# stm32f4.net
KiCad netlist of a schematic drawn in EAGLE
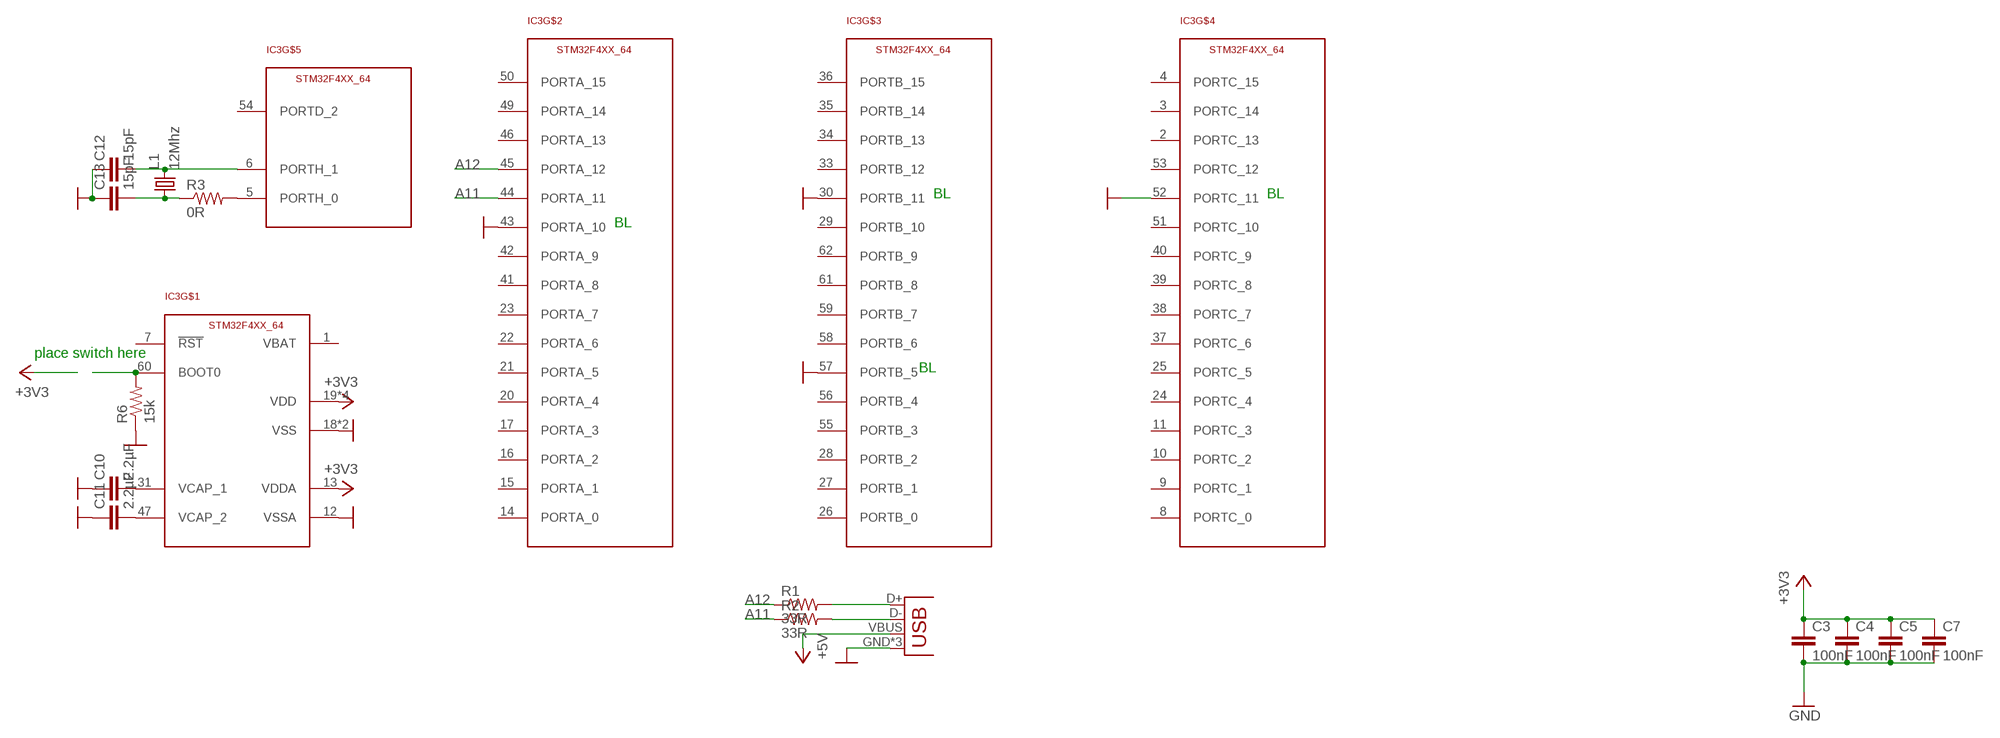
[diagram p0: schematic, sheet 1]

(export (version "E")
  (design (tool "Eeschema 10.0.6"))
  (components
    (comp (ref "C3")
      (value "100nF")
      (footprint "eagle-import:0402-CAP")
      (libsource (lib "eagle-import") (part "CAP0402-CAP"))
    )
    (comp (ref "C4")
      (value "100nF")
      (footprint "eagle-import:0402-CAP")
      (libsource (lib "eagle-import") (part "CAP0402-CAP"))
    )
    (comp (ref "C5")
      (value "100nF")
      (footprint "eagle-import:0402-CAP")
      (libsource (lib "eagle-import") (part "CAP0402-CAP"))
    )
    (comp (ref "C7")
      (value "100nF")
      (footprint "eagle-import:0402-CAP")
      (libsource (lib "eagle-import") (part "CAP0402-CAP"))
    )
    (comp (ref "C10")
      (value "2.2µF")
      (footprint "eagle-import:0805")
      (libsource (lib "eagle-import") (part "CAP0805"))
    )
    (comp (ref "C11")
      (value "2.2µF")
      (footprint "eagle-import:0805")
      (libsource (lib "eagle-import") (part "CAP0805"))
    )
    (comp (ref "C12")
      (value "15pF")
      (footprint "eagle-import:0402-CAP")
      (libsource (lib "eagle-import") (part "CAP0402-CAP"))
    )
    (comp (ref "C13")
      (value "15pF")
      (footprint "eagle-import:0402-CAP")
      (libsource (lib "eagle-import") (part "CAP0402-CAP"))
    )
    (comp (ref "IC3")
      (value "STM32F4XX_64")
      (footprint "eagle-import:TQFP64")
      (libsource (lib "eagle-import") (part "STM32F4XX_64"))
    )
    (comp (ref "JP1")
      (value "USB-MICROB")
      (footprint "eagle-import:USB-MICROB")
      (libsource (lib "eagle-import") (part "USB-MICROB"))
    )
    (comp (ref "L1")
      (value "12Mhz")
      (footprint "eagle-import:X22")
      (libsource (lib "eagle-import") (part "X22-OSCILLATOR"))
    )
    (comp (ref "R1")
      (value "33R")
      (footprint "eagle-import:0402-RES")
      (libsource (lib "eagle-import") (part "SparkFun-Resistors_RESISTOR0402-RES"))
    )
    (comp (ref "R2")
      (value "33R")
      (footprint "eagle-import:0402-RES")
      (libsource (lib "eagle-import") (part "SparkFun-Resistors_RESISTOR0402-RES"))
    )
    (comp (ref "R3")
      (value "0R")
      (footprint "eagle-import:0402-RES")
      (libsource (lib "eagle-import") (part "SparkFun-Resistors_RESISTOR0402-RES"))
    )
    (comp (ref "R6")
      (value "15k")
      (footprint "eagle-import:0402-RES")
      (libsource (lib "eagle-import") (part "RESISTOR0402-RES"))
    )
  )
  (nets
    (net (code "1") (name "+3V3") (class "Default")
      (node (ref "C3") (pin "1") (pinfunction "1_1") (pintype "passive"))
      (node (ref "C4") (pin "1") (pinfunction "1_1") (pintype "passive"))
      (node (ref "C5") (pin "1") (pinfunction "1_1") (pintype "passive"))
      (node (ref "C7") (pin "1") (pinfunction "1_1") (pintype "passive"))
      (node (ref "IC3") (pin "13") (pinfunction "VDDA_13") (pintype "bidirectional"))
      (node (ref "IC3") (pin "19") (pinfunction "VDD_19") (pintype "bidirectional"))
      (node (ref "IC3") (pin "32") (pinfunction "VDD_32") (pintype "bidirectional"))
      (node (ref "IC3") (pin "48") (pinfunction "VDD_48") (pintype "bidirectional"))
      (node (ref "IC3") (pin "64") (pinfunction "VDD_64") (pintype "bidirectional"))
    )
    (net (code "2") (name "+5V") (class "Default")
      (node (ref "JP1") (pin "VBUS") (pinfunction "VBUS_VBUS") (pintype "bidirectional"))
    )
    (net (code "3") (name "/A11") (class "Default")
      (node (ref "IC3") (pin "44") (pinfunction "PORTA_11_44") (pintype "bidirectional"))
      (node (ref "R2") (pin "1") (pinfunction "1_1") (pintype "passive"))
    )
    (net (code "4") (name "/A12") (class "Default")
      (node (ref "IC3") (pin "45") (pinfunction "PORTA_12_45") (pintype "bidirectional"))
      (node (ref "R1") (pin "1") (pinfunction "1_1") (pintype "passive"))
    )
    (net (code "5") (name "GND") (class "Default")
      (node (ref "C10") (pin "1") (pinfunction "1_1") (pintype "passive"))
      (node (ref "C11") (pin "1") (pinfunction "1_1") (pintype "passive"))
      (node (ref "C12") (pin "1") (pinfunction "1_1") (pintype "passive"))
      (node (ref "C13") (pin "1") (pinfunction "1_1") (pintype "passive"))
      (node (ref "C3") (pin "2") (pinfunction "2_2") (pintype "passive"))
      (node (ref "C4") (pin "2") (pinfunction "2_2") (pintype "passive"))
      (node (ref "C5") (pin "2") (pinfunction "2_2") (pintype "passive"))
      (node (ref "C7") (pin "2") (pinfunction "2_2") (pintype "passive"))
      (node (ref "IC3") (pin "12") (pinfunction "VSSA_12") (pintype "bidirectional"))
      (node (ref "IC3") (pin "18") (pinfunction "VSS_18") (pintype "bidirectional"))
      (node (ref "IC3") (pin "30") (pinfunction "PORTB_11_30") (pintype "bidirectional"))
      (node (ref "IC3") (pin "43") (pinfunction "PORTA_10_43") (pintype "bidirectional"))
      (node (ref "IC3") (pin "52") (pinfunction "PORTC_11_52") (pintype "bidirectional"))
      (node (ref "IC3") (pin "57") (pinfunction "PORTB_5_57") (pintype "bidirectional"))
      (node (ref "IC3") (pin "63") (pinfunction "VSS_63") (pintype "bidirectional"))
      (node (ref "JP1") (pin "GND") (pinfunction "GND_GND") (pintype "bidirectional"))
      (node (ref "JP1") (pin "MT1") (pinfunction "GND_MT1") (pintype "bidirectional"))
      (node (ref "JP1") (pin "MT2") (pinfunction "GND_MT2") (pintype "bidirectional"))
      (node (ref "R6") (pin "1") (pinfunction "1_1") (pintype "passive"))
    )
    (net (code "6") (name "Net-(C13-Pad2)") (class "Default")
      (node (ref "C13") (pin "2") (pinfunction "2_2") (pintype "passive"))
      (node (ref "L1") (pin "1") (pinfunction "1_1") (pintype "passive"))
      (node (ref "R3") (pin "1") (pinfunction "1_1") (pintype "passive"))
    )
    (net (code "7") (name "Net-(IC3A-BOOT0)") (class "Default")
      (node (ref "IC3") (pin "60") (pinfunction "BOOT0_60") (pintype "bidirectional"))
      (node (ref "R6") (pin "2") (pinfunction "2_2") (pintype "passive"))
    )
    (net (code "8") (name "Net-(IC3A-VCAP_1)") (class "Default")
      (node (ref "C10") (pin "2") (pinfunction "2_2") (pintype "passive"))
      (node (ref "IC3") (pin "31") (pinfunction "VCAP_1_31") (pintype "bidirectional"))
    )
    (net (code "9") (name "Net-(IC3A-VCAP_2)") (class "Default")
      (node (ref "C11") (pin "2") (pinfunction "2_2") (pintype "passive"))
      (node (ref "IC3") (pin "47") (pinfunction "VCAP_2_47") (pintype "bidirectional"))
    )
    (net (code "10") (name "Net-(IC3E-PORTH_0)") (class "Default")
      (node (ref "IC3") (pin "5") (pinfunction "PORTH_0_5") (pintype "bidirectional"))
      (node (ref "R3") (pin "2") (pinfunction "2_2") (pintype "passive"))
    )
    (net (code "11") (name "Net-(IC3E-PORTH_1)") (class "Default")
      (node (ref "C12") (pin "2") (pinfunction "2_2") (pintype "passive"))
      (node (ref "IC3") (pin "6") (pinfunction "PORTH_1_6") (pintype "bidirectional"))
      (node (ref "L1") (pin "3") (pinfunction "2_3") (pintype "passive"))
    )
    (net (code "12") (name "Net-(JP1-PadD+)") (class "Default")
      (node (ref "JP1") (pin "D+") (pinfunction "D+_D+") (pintype "bidirectional"))
      (node (ref "R1") (pin "2") (pinfunction "2_2") (pintype "passive"))
    )
    (net (code "13") (name "Net-(JP1-PadD-)") (class "Default")
      (node (ref "JP1") (pin "D-") (pinfunction "D-_D-") (pintype "bidirectional"))
      (node (ref "R2") (pin "2") (pinfunction "2_2") (pintype "passive"))
    )
    (net (code "14") (name "unconnected-(IC3A-VBAT-Pad1)") (class "Default")
      (node (ref "IC3") (pin "1") (pinfunction "VBAT_1") (pintype "bidirectional"))
    )
    (net (code "15") (name "unconnected-(IC3A-~{RST}-Pad7)") (class "Default")
      (node (ref "IC3") (pin "7") (pinfunction "~{RST}_7") (pintype "bidirectional"))
    )
    (net (code "16") (name "unconnected-(IC3B-PORTA_0-Pad14)") (class "Default")
      (node (ref "IC3") (pin "14") (pinfunction "PORTA_0_14") (pintype "bidirectional"))
    )
    (net (code "17") (name "unconnected-(IC3B-PORTA_1-Pad15)") (class "Default")
      (node (ref "IC3") (pin "15") (pinfunction "PORTA_1_15") (pintype "bidirectional"))
    )
    (net (code "18") (name "unconnected-(IC3B-PORTA_2-Pad16)") (class "Default")
      (node (ref "IC3") (pin "16") (pinfunction "PORTA_2_16") (pintype "bidirectional"))
    )
    (net (code "19") (name "unconnected-(IC3B-PORTA_3-Pad17)") (class "Default")
      (node (ref "IC3") (pin "17") (pinfunction "PORTA_3_17") (pintype "bidirectional"))
    )
    (net (code "20") (name "unconnected-(IC3B-PORTA_4-Pad20)") (class "Default")
      (node (ref "IC3") (pin "20") (pinfunction "PORTA_4_20") (pintype "bidirectional"))
    )
    (net (code "21") (name "unconnected-(IC3B-PORTA_5-Pad21)") (class "Default")
      (node (ref "IC3") (pin "21") (pinfunction "PORTA_5_21") (pintype "bidirectional"))
    )
    (net (code "22") (name "unconnected-(IC3B-PORTA_6-Pad22)") (class "Default")
      (node (ref "IC3") (pin "22") (pinfunction "PORTA_6_22") (pintype "bidirectional"))
    )
    (net (code "23") (name "unconnected-(IC3B-PORTA_7-Pad23)") (class "Default")
      (node (ref "IC3") (pin "23") (pinfunction "PORTA_7_23") (pintype "bidirectional"))
    )
    (net (code "24") (name "unconnected-(IC3B-PORTA_8-Pad41)") (class "Default")
      (node (ref "IC3") (pin "41") (pinfunction "PORTA_8_41") (pintype "bidirectional"))
    )
    (net (code "25") (name "unconnected-(IC3B-PORTA_9-Pad42)") (class "Default")
      (node (ref "IC3") (pin "42") (pinfunction "PORTA_9_42") (pintype "bidirectional"))
    )
    (net (code "26") (name "unconnected-(IC3B-PORTA_13-Pad46)") (class "Default")
      (node (ref "IC3") (pin "46") (pinfunction "PORTA_13_46") (pintype "bidirectional"))
    )
    (net (code "27") (name "unconnected-(IC3B-PORTA_14-Pad49)") (class "Default")
      (node (ref "IC3") (pin "49") (pinfunction "PORTA_14_49") (pintype "bidirectional"))
    )
    (net (code "28") (name "unconnected-(IC3B-PORTA_15-Pad50)") (class "Default")
      (node (ref "IC3") (pin "50") (pinfunction "PORTA_15_50") (pintype "bidirectional"))
    )
    (net (code "29") (name "unconnected-(IC3C-PORTB_0-Pad26)") (class "Default")
      (node (ref "IC3") (pin "26") (pinfunction "PORTB_0_26") (pintype "bidirectional"))
    )
    (net (code "30") (name "unconnected-(IC3C-PORTB_1-Pad27)") (class "Default")
      (node (ref "IC3") (pin "27") (pinfunction "PORTB_1_27") (pintype "bidirectional"))
    )
    (net (code "31") (name "unconnected-(IC3C-PORTB_2-Pad28)") (class "Default")
      (node (ref "IC3") (pin "28") (pinfunction "PORTB_2_28") (pintype "bidirectional"))
    )
    (net (code "32") (name "unconnected-(IC3C-PORTB_3-Pad55)") (class "Default")
      (node (ref "IC3") (pin "55") (pinfunction "PORTB_3_55") (pintype "bidirectional"))
    )
    (net (code "33") (name "unconnected-(IC3C-PORTB_4-Pad56)") (class "Default")
      (node (ref "IC3") (pin "56") (pinfunction "PORTB_4_56") (pintype "bidirectional"))
    )
    (net (code "34") (name "unconnected-(IC3C-PORTB_6-Pad58)") (class "Default")
      (node (ref "IC3") (pin "58") (pinfunction "PORTB_6_58") (pintype "bidirectional"))
    )
    (net (code "35") (name "unconnected-(IC3C-PORTB_7-Pad59)") (class "Default")
      (node (ref "IC3") (pin "59") (pinfunction "PORTB_7_59") (pintype "bidirectional"))
    )
    (net (code "36") (name "unconnected-(IC3C-PORTB_8-Pad61)") (class "Default")
      (node (ref "IC3") (pin "61") (pinfunction "PORTB_8_61") (pintype "bidirectional"))
    )
    (net (code "37") (name "unconnected-(IC3C-PORTB_9-Pad62)") (class "Default")
      (node (ref "IC3") (pin "62") (pinfunction "PORTB_9_62") (pintype "bidirectional"))
    )
    (net (code "38") (name "unconnected-(IC3C-PORTB_10-Pad29)") (class "Default")
      (node (ref "IC3") (pin "29") (pinfunction "PORTB_10_29") (pintype "bidirectional"))
    )
    (net (code "39") (name "unconnected-(IC3C-PORTB_12-Pad33)") (class "Default")
      (node (ref "IC3") (pin "33") (pinfunction "PORTB_12_33") (pintype "bidirectional"))
    )
    (net (code "40") (name "unconnected-(IC3C-PORTB_13-Pad34)") (class "Default")
      (node (ref "IC3") (pin "34") (pinfunction "PORTB_13_34") (pintype "bidirectional"))
    )
    (net (code "41") (name "unconnected-(IC3C-PORTB_14-Pad35)") (class "Default")
      (node (ref "IC3") (pin "35") (pinfunction "PORTB_14_35") (pintype "bidirectional"))
    )
    (net (code "42") (name "unconnected-(IC3C-PORTB_15-Pad36)") (class "Default")
      (node (ref "IC3") (pin "36") (pinfunction "PORTB_15_36") (pintype "bidirectional"))
    )
    (net (code "43") (name "unconnected-(IC3D-PORTC_0-Pad8)") (class "Default")
      (node (ref "IC3") (pin "8") (pinfunction "PORTC_0_8") (pintype "bidirectional"))
    )
    (net (code "44") (name "unconnected-(IC3D-PORTC_1-Pad9)") (class "Default")
      (node (ref "IC3") (pin "9") (pinfunction "PORTC_1_9") (pintype "bidirectional"))
    )
    (net (code "45") (name "unconnected-(IC3D-PORTC_2-Pad10)") (class "Default")
      (node (ref "IC3") (pin "10") (pinfunction "PORTC_2_10") (pintype "bidirectional"))
    )
    (net (code "46") (name "unconnected-(IC3D-PORTC_3-Pad11)") (class "Default")
      (node (ref "IC3") (pin "11") (pinfunction "PORTC_3_11") (pintype "bidirectional"))
    )
    (net (code "47") (name "unconnected-(IC3D-PORTC_4-Pad24)") (class "Default")
      (node (ref "IC3") (pin "24") (pinfunction "PORTC_4_24") (pintype "bidirectional"))
    )
    (net (code "48") (name "unconnected-(IC3D-PORTC_5-Pad25)") (class "Default")
      (node (ref "IC3") (pin "25") (pinfunction "PORTC_5_25") (pintype "bidirectional"))
    )
    (net (code "49") (name "unconnected-(IC3D-PORTC_6-Pad37)") (class "Default")
      (node (ref "IC3") (pin "37") (pinfunction "PORTC_6_37") (pintype "bidirectional"))
    )
    (net (code "50") (name "unconnected-(IC3D-PORTC_7-Pad38)") (class "Default")
      (node (ref "IC3") (pin "38") (pinfunction "PORTC_7_38") (pintype "bidirectional"))
    )
    (net (code "51") (name "unconnected-(IC3D-PORTC_8-Pad39)") (class "Default")
      (node (ref "IC3") (pin "39") (pinfunction "PORTC_8_39") (pintype "bidirectional"))
    )
    (net (code "52") (name "unconnected-(IC3D-PORTC_9-Pad40)") (class "Default")
      (node (ref "IC3") (pin "40") (pinfunction "PORTC_9_40") (pintype "bidirectional"))
    )
    (net (code "53") (name "unconnected-(IC3D-PORTC_10-Pad51)") (class "Default")
      (node (ref "IC3") (pin "51") (pinfunction "PORTC_10_51") (pintype "bidirectional"))
    )
    (net (code "54") (name "unconnected-(IC3D-PORTC_12-Pad53)") (class "Default")
      (node (ref "IC3") (pin "53") (pinfunction "PORTC_12_53") (pintype "bidirectional"))
    )
    (net (code "55") (name "unconnected-(IC3D-PORTC_13-Pad2)") (class "Default")
      (node (ref "IC3") (pin "2") (pinfunction "PORTC_13_2") (pintype "bidirectional"))
    )
    (net (code "56") (name "unconnected-(IC3D-PORTC_14-Pad3)") (class "Default")
      (node (ref "IC3") (pin "3") (pinfunction "PORTC_14_3") (pintype "bidirectional"))
    )
    (net (code "57") (name "unconnected-(IC3D-PORTC_15-Pad4)") (class "Default")
      (node (ref "IC3") (pin "4") (pinfunction "PORTC_15_4") (pintype "bidirectional"))
    )
    (net (code "58") (name "unconnected-(IC3E-PORTD_2-Pad54)") (class "Default")
      (node (ref "IC3") (pin "54") (pinfunction "PORTD_2_54") (pintype "bidirectional"))
    )
  )
)
